# openSX70_SCHEMATIC_COMPLETE_NEW_BOARD_CO.net
KiCad netlist of a schematic drawn in EAGLE
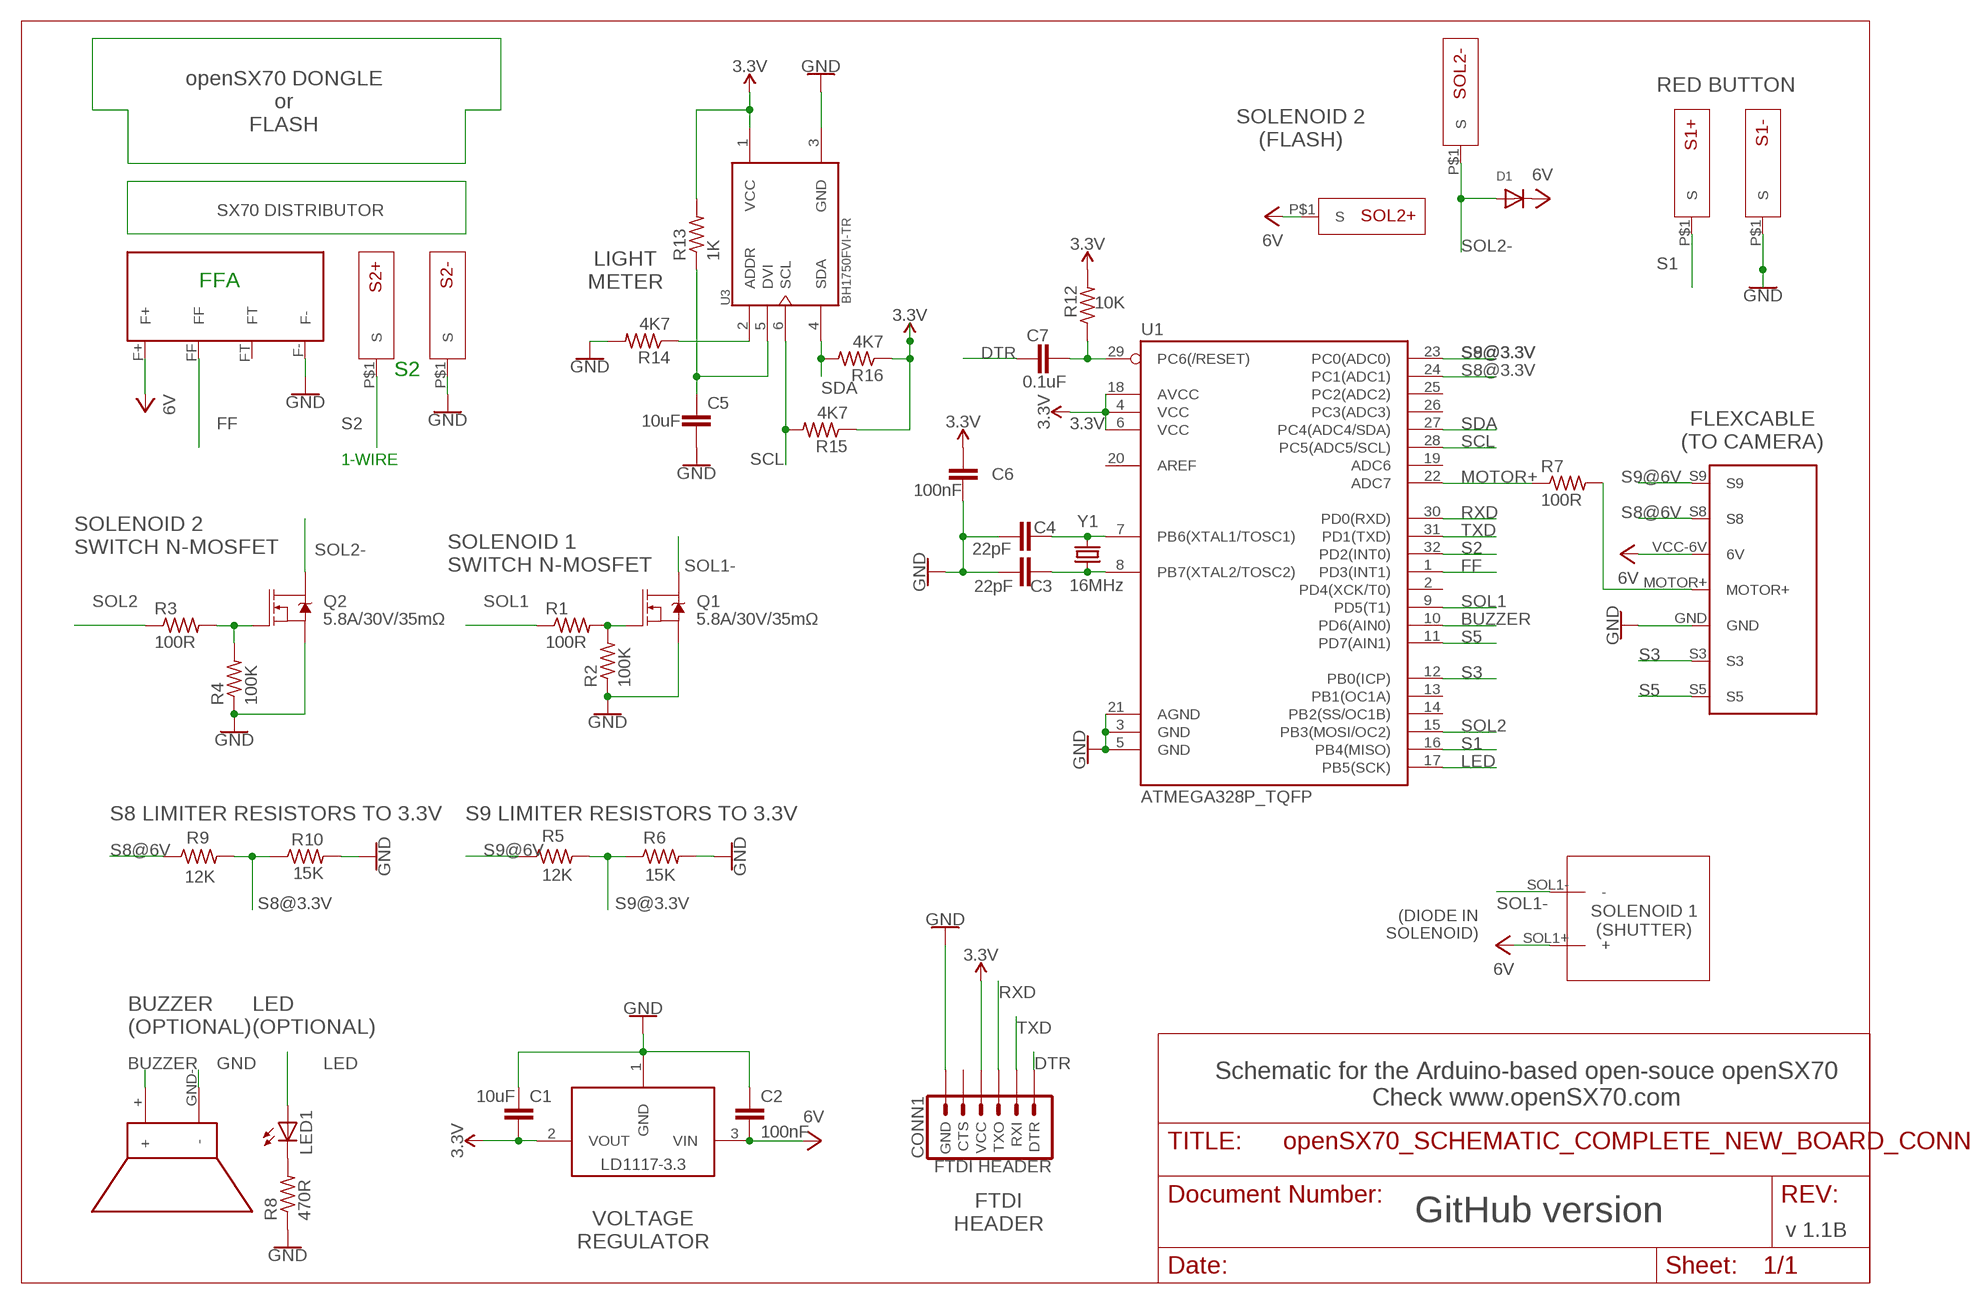
[diagram p0: schematic, sheet 1]

(export (version "E")
  (design (tool "Eeschema 10.0.6"))
  (components
    (comp (ref "BUZZ1")
      (value "CSET8-5G")
      (footprint "eagle-import:CSET8-5G_PACKAGE")
      (libsource (lib "eagle-import") (part "CSET8-5G"))
    )
    (comp (ref "C1")
      (value "10uF")
      (footprint "eagle-import:0603")
      (libsource (lib "eagle-import") (part "10UF-0603-6.3V-20%"))
    )
    (comp (ref "C2")
      (value "100nF")
      (footprint "eagle-import:C0603K")
      (libsource (lib "eagle-import") (part "C-EUC0603K"))
    )
    (comp (ref "C3")
      (value "22pF")
      (footprint "eagle-import:0603")
      (libsource (lib "eagle-import") (part "22PF-0603-50V-5%"))
    )
    (comp (ref "C4")
      (value "22pF")
      (footprint "eagle-import:0603")
      (libsource (lib "eagle-import") (part "22PF-0603-50V-5%"))
    )
    (comp (ref "C5")
      (value "10uF")
      (footprint "eagle-import:0603")
      (libsource (lib "eagle-import") (part "10UF-0603-6.3V-20%"))
    )
    (comp (ref "C6")
      (value "100nF")
      (footprint "eagle-import:C0805")
      (libsource (lib "eagle-import") (part "resistor_C-EUC0805"))
    )
    (comp (ref "C7")
      (value "0.1uF")
      (footprint "eagle-import:0603")
      (libsource (lib "eagle-import") (part "0.1UF-0603-25V-(+80/-20%)"))
    )
    (comp (ref "CONN1")
      (value "FTDI HEADER")
      (footprint "eagle-import:1X06")
      (libsource (lib "eagle-import") (part "6_PIN_SERIAL_TARGET"))
    )
    (comp (ref "D1")
      (value "DIODESOD-523")
      (footprint "eagle-import:SOD-523")
      (libsource (lib "eagle-import") (part "DIODESOD-523"))
    )
    (comp (ref "LD11173.3V")
      (value "LD1117 3.3V")
      (footprint "eagle-import:SOT223")
      (fields (field (name "MF") "Advanced Monolithic Systems") (field (name "MP") "AMS1117-5.0"))
      (libsource (lib "eagle-import") (part "LD1117-3.3"))
    )
    (comp (ref "LED1")
      (value "LEDCHIPLED_0805")
      (footprint "eagle-import:CHIPLED_0805")
      (libsource (lib "eagle-import") (part "LEDCHIPLED_0805"))
    )
    (comp (ref "Q1")
      (value "5.8A/30V/35mΩ")
      (footprint "eagle-import:SOT23-3")
      (libsource (lib "eagle-import") (part "MOSFET-NCH-AO3404A"))
    )
    (comp (ref "Q2")
      (value "5.8A/30V/35mΩ")
      (footprint "eagle-import:SOT23-3")
      (libsource (lib "eagle-import") (part "MOSFET-NCH-AO3404A"))
    )
    (comp (ref "R1")
      (value "100R")
      (footprint "eagle-import:R0603")
      (libsource (lib "eagle-import") (part "R-US_R0603"))
    )
    (comp (ref "R2")
      (value "100K")
      (footprint "eagle-import:R0603")
      (libsource (lib "eagle-import") (part "R-US_R0603"))
    )
    (comp (ref "R3")
      (value "100R")
      (footprint "eagle-import:R0603")
      (libsource (lib "eagle-import") (part "R-US_R0603"))
    )
    (comp (ref "R4")
      (value "100K")
      (footprint "eagle-import:R0603")
      (libsource (lib "eagle-import") (part "R-US_R0603"))
    )
    (comp (ref "R5")
      (value "12K")
      (footprint "eagle-import:R0603")
      (libsource (lib "eagle-import") (part "R-US_R0603"))
    )
    (comp (ref "R6")
      (value "15K")
      (footprint "eagle-import:R0603")
      (libsource (lib "eagle-import") (part "R-US_R0603"))
    )
    (comp (ref "R7")
      (value "100R")
      (footprint "eagle-import:R0603")
      (libsource (lib "eagle-import") (part "R-US_R0603"))
    )
    (comp (ref "R8")
      (value "470R")
      (footprint "eagle-import:R0603")
      (libsource (lib "eagle-import") (part "R-US_R0603"))
    )
    (comp (ref "R9")
      (value "12K")
      (footprint "eagle-import:R0603")
      (libsource (lib "eagle-import") (part "R-US_R0603"))
    )
    (comp (ref "R10")
      (value "15K")
      (footprint "eagle-import:R0603")
      (libsource (lib "eagle-import") (part "R-US_R0603"))
    )
    (comp (ref "R12")
      (value "10K")
      (footprint "eagle-import:R0603")
      (libsource (lib "eagle-import") (part "R-US_R0603"))
    )
    (comp (ref "R13")
      (value "1K")
      (footprint "eagle-import:R0603")
      (libsource (lib "eagle-import") (part "R-US_R0603"))
    )
    (comp (ref "R14")
      (value "4K7")
      (footprint "eagle-import:R0603")
      (libsource (lib "eagle-import") (part "R-US_R0603"))
    )
    (comp (ref "R15")
      (value "4K7")
      (footprint "eagle-import:R0603")
      (libsource (lib "eagle-import") (part "R-US_R0603"))
    )
    (comp (ref "R16")
      (value "4K7")
      (footprint "eagle-import:R0603")
      (libsource (lib "eagle-import") (part "R-US_R0603"))
    )
    (comp (ref "S1+")
      (value "SX70_S-PAD")
      (footprint "eagle-import:SX70-S-PAD")
      (libsource (lib "eagle-import") (part "SX70_S-PAD"))
    )
    (comp (ref "S1-")
      (value "SX70_S-PAD")
      (footprint "eagle-import:SX70-S-PAD")
      (libsource (lib "eagle-import") (part "SX70_S-PAD"))
    )
    (comp (ref "S2+")
      (value "SX70_S-PAD")
      (footprint "eagle-import:SX70-S-PAD")
      (libsource (lib "eagle-import") (part "SX70_S-PAD"))
    )
    (comp (ref "S2-")
      (value "SX70_S-PAD")
      (footprint "eagle-import:SX70-S-PAD")
      (libsource (lib "eagle-import") (part "SX70_S-PAD"))
    )
    (comp (ref "SOL1")
      (value "SX70-SOLENOID1-2PADS")
      (footprint "eagle-import:SX70-SOLENOID1-2")
      (libsource (lib "eagle-import") (part "SX70-SOLENOID1-2PADS"))
    )
    (comp (ref "SOL2+")
      (value "SX70_S-PAD")
      (footprint "eagle-import:SX70-S-PAD")
      (libsource (lib "eagle-import") (part "SX70_S-PAD"))
    )
    (comp (ref "SOL2-")
      (value "SX70_S-PAD")
      (footprint "eagle-import:SX70-S-PAD")
      (libsource (lib "eagle-import") (part "SX70_S-PAD"))
    )
    (comp (ref "U$1")
      (value "SX70-7-PAD")
      (footprint "eagle-import:SX70-7-PAD")
      (libsource (lib "eagle-import") (part "SX70-7-PAD"))
    )
    (comp (ref "U$2")
      (value "SX70-FFA-PAD")
      (footprint "eagle-import:FFA-PAD-PACKAGE")
      (libsource (lib "eagle-import") (part "SX70-FFA-PAD"))
    )
    (comp (ref "U1")
      (value "ATMEGA328P_TQFP")
      (footprint "eagle-import:TQFP32-08")
      (libsource (lib "eagle-import") (part "ATMEGA328P_TQFP"))
    )
    (comp (ref "U3")
      (value "BH1750FVI-TR")
      (footprint "eagle-import:SOTFL50P300X75-6N")
      (fields (field (name "MF") "Rohm"))
      (libsource (lib "eagle-import") (part "BH1750FVI-TR"))
    )
    (comp (ref "Y1")
      (value "16MHz")
      (footprint "eagle-import:CRYSTAL-SMD-5X3.2-4PAD")
      (libsource (lib "eagle-import") (part "CRYSTAL-16MHZSMD-5X3.2"))
    )
  )
  (nets
    (net (code "1") (name "/BUZZER") (class "Default")
      (node (ref "BUZZ1") (pin "+") (pinfunction "+_+") (pintype "bidirectional"))
      (node (ref "U1") (pin "10") (pinfunction "PD6(AIN0)_10") (pintype "bidirectional"))
    )
    (net (code "2") (name "/DTR") (class "Default")
      (node (ref "C7") (pin "1") (pinfunction "1_1") (pintype "passive"))
      (node (ref "CONN1") (pin "1") (pinfunction "DTR_1") (pintype "passive"))
    )
    (net (code "3") (name "/FF") (class "Default")
      (node (ref "U$2") (pin "FF") (pinfunction "FF_FF") (pintype "bidirectional"))
      (node (ref "U1") (pin "1") (pinfunction "PD3(INT1)_1") (pintype "bidirectional"))
    )
    (net (code "4") (name "/LED") (class "Default")
      (node (ref "LED1") (pin "A") (pinfunction "A_A") (pintype "passive"))
      (node (ref "U1") (pin "17") (pinfunction "PB5(SCK)_17") (pintype "bidirectional"))
    )
    (net (code "5") (name "/MOTOR+") (class "Default")
      (node (ref "R7") (pin "1") (pinfunction "1_1") (pintype "passive"))
      (node (ref "U1") (pin "22") (pinfunction "ADC7_22") (pintype "bidirectional"))
    )
    (net (code "6") (name "/RXD") (class "Default")
      (node (ref "CONN1") (pin "3") (pinfunction "TXO_3") (pintype "passive"))
      (node (ref "U1") (pin "30") (pinfunction "PD0(RXD)_30") (pintype "bidirectional"))
    )
    (net (code "7") (name "/S1") (class "Default")
      (node (ref "S1+") (pin "P$1") (pinfunction "S_P$1") (pintype "bidirectional"))
      (node (ref "U1") (pin "16") (pinfunction "PB4(MISO)_16") (pintype "bidirectional"))
    )
    (net (code "8") (name "/S2") (class "Default")
      (node (ref "S2+") (pin "P$1") (pinfunction "S_P$1") (pintype "bidirectional"))
      (node (ref "U1") (pin "32") (pinfunction "PD2(INT0)_32") (pintype "bidirectional"))
    )
    (net (code "9") (name "/S3") (class "Default")
      (node (ref "U$1") (pin "S3") (pinfunction "S3_S3") (pintype "bidirectional"))
      (node (ref "U1") (pin "12") (pinfunction "PB0(ICP)_12") (pintype "bidirectional"))
    )
    (net (code "10") (name "/S5") (class "Default")
      (node (ref "U$1") (pin "S5") (pinfunction "S5_S5") (pintype "bidirectional"))
      (node (ref "U1") (pin "11") (pinfunction "PD7(AIN1)_11") (pintype "bidirectional"))
    )
    (net (code "11") (name "/S8@3.3V") (class "Default")
      (node (ref "R10") (pin "1") (pinfunction "1_1") (pintype "passive"))
      (node (ref "R9") (pin "2") (pinfunction "2_2") (pintype "passive"))
      (node (ref "U1") (pin "24") (pinfunction "PC1(ADC1)_24") (pintype "bidirectional"))
    )
    (net (code "12") (name "/S8@6V") (class "Default")
      (node (ref "R9") (pin "1") (pinfunction "1_1") (pintype "passive"))
      (node (ref "U$1") (pin "S8") (pinfunction "S8_S8") (pintype "bidirectional"))
    )
    (net (code "13") (name "/S9@3.3V") (class "Default")
      (node (ref "R5") (pin "2") (pinfunction "2_2") (pintype "passive"))
      (node (ref "R6") (pin "1") (pinfunction "1_1") (pintype "passive"))
      (node (ref "U1") (pin "23") (pinfunction "PC0(ADC0)_23") (pintype "bidirectional"))
    )
    (net (code "14") (name "/S9@6V") (class "Default")
      (node (ref "R5") (pin "1") (pinfunction "1_1") (pintype "passive"))
      (node (ref "U$1") (pin "S9") (pinfunction "S9_S9") (pintype "bidirectional"))
    )
    (net (code "15") (name "/SCL") (class "Default")
      (node (ref "R15") (pin "2") (pinfunction "2_2") (pintype "passive"))
      (node (ref "U1") (pin "28") (pinfunction "PC5(ADC5/SCL)_28") (pintype "bidirectional"))
      (node (ref "U3") (pin "6") (pinfunction "SCL_6") (pintype "input"))
    )
    (net (code "16") (name "/SDA") (class "Default")
      (node (ref "R16") (pin "2") (pinfunction "2_2") (pintype "passive"))
      (node (ref "U1") (pin "27") (pinfunction "PC4(ADC4/SDA)_27") (pintype "bidirectional"))
      (node (ref "U3") (pin "4") (pinfunction "SDA_4") (pintype "bidirectional"))
    )
    (net (code "17") (name "/SOL1") (class "Default")
      (node (ref "R1") (pin "1") (pinfunction "1_1") (pintype "passive"))
      (node (ref "U1") (pin "9") (pinfunction "PD5(T1)_9") (pintype "bidirectional"))
    )
    (net (code "18") (name "/SOL1-") (class "Default")
      (node (ref "Q1") (pin "3") (pinfunction "D_3") (pintype "bidirectional"))
      (node (ref "SOL1") (pin "SOL1-") (pinfunction "-_SOL1-") (pintype "bidirectional"))
    )
    (net (code "19") (name "/SOL2") (class "Default")
      (node (ref "R3") (pin "1") (pinfunction "1_1") (pintype "passive"))
      (node (ref "U1") (pin "15") (pinfunction "PB3(MOSI/OC2)_15") (pintype "bidirectional"))
    )
    (net (code "20") (name "/SOL2-") (class "Default")
      (node (ref "D1") (pin "A") (pinfunction "A_A") (pintype "passive"))
      (node (ref "Q2") (pin "3") (pinfunction "D_3") (pintype "bidirectional"))
      (node (ref "SOL2-") (pin "P$1") (pinfunction "S_P$1") (pintype "bidirectional"))
    )
    (net (code "21") (name "/TXD") (class "Default")
      (node (ref "CONN1") (pin "2") (pinfunction "RXI_2") (pintype "passive"))
      (node (ref "U1") (pin "31") (pinfunction "PD1(TXD)_31") (pintype "bidirectional"))
    )
    (net (code "22") (name "3.3V") (class "Default")
      (node (ref "C1") (pin "2") (pinfunction "2_2") (pintype "passive"))
      (node (ref "C6") (pin "1") (pinfunction "1_1") (pintype "passive"))
      (node (ref "CONN1") (pin "4") (pinfunction "VCC_4") (pintype "passive"))
      (node (ref "LD11173.3V") (pin "2") (pinfunction "VOUT_2") (pintype "bidirectional"))
      (node (ref "R12") (pin "2") (pinfunction "2_2") (pintype "passive"))
      (node (ref "R13") (pin "2") (pinfunction "2_2") (pintype "passive"))
      (node (ref "R15") (pin "1") (pinfunction "1_1") (pintype "passive"))
      (node (ref "R16") (pin "1") (pinfunction "1_1") (pintype "passive"))
      (node (ref "U1") (pin "18") (pinfunction "AVCC_18") (pintype "bidirectional"))
      (node (ref "U1") (pin "4") (pinfunction "VCC_4") (pintype "bidirectional"))
      (node (ref "U1") (pin "6") (pinfunction "VCC_6") (pintype "bidirectional"))
      (node (ref "U3") (pin "1") (pinfunction "VCC_1") (pintype "power_in"))
    )
    (net (code "23") (name "6V") (class "Default")
      (node (ref "C2") (pin "2") (pinfunction "2_2") (pintype "passive"))
      (node (ref "D1") (pin "K") (pinfunction "C_K") (pintype "passive"))
      (node (ref "LD11173.3V") (pin "3") (pinfunction "VIN_3") (pintype "bidirectional"))
      (node (ref "SOL1") (pin "SOL1+") (pinfunction "+_SOL1+") (pintype "bidirectional"))
      (node (ref "SOL2+") (pin "P$1") (pinfunction "S_P$1") (pintype "bidirectional"))
      (node (ref "U$1") (pin "VCC-6V") (pinfunction "6V_VCC-6V") (pintype "bidirectional"))
      (node (ref "U$2") (pin "F+") (pinfunction "F+_F+") (pintype "bidirectional"))
    )
    (net (code "24") (name "GND") (class "Default")
      (node (ref "BUZZ1") (pin "GND-") (pinfunction "-_GND-") (pintype "bidirectional"))
      (node (ref "C1") (pin "1") (pinfunction "1_1") (pintype "passive"))
      (node (ref "C2") (pin "1") (pinfunction "1_1") (pintype "passive"))
      (node (ref "C3") (pin "1") (pinfunction "1_1") (pintype "passive"))
      (node (ref "C4") (pin "1") (pinfunction "1_1") (pintype "passive"))
      (node (ref "C5") (pin "2") (pinfunction "2_2") (pintype "passive"))
      (node (ref "C6") (pin "2") (pinfunction "2_2") (pintype "passive"))
      (node (ref "CONN1") (pin "6") (pinfunction "GND_6") (pintype "passive"))
      (node (ref "LD11173.3V") (pin "1") (pinfunction "GND_1") (pintype "bidirectional"))
      (node (ref "Q1") (pin "2") (pinfunction "S_2") (pintype "bidirectional"))
      (node (ref "Q2") (pin "2") (pinfunction "S_2") (pintype "bidirectional"))
      (node (ref "R10") (pin "2") (pinfunction "2_2") (pintype "passive"))
      (node (ref "R14") (pin "2") (pinfunction "2_2") (pintype "passive"))
      (node (ref "R2") (pin "1") (pinfunction "1_1") (pintype "passive"))
      (node (ref "R4") (pin "1") (pinfunction "1_1") (pintype "passive"))
      (node (ref "R6") (pin "2") (pinfunction "2_2") (pintype "passive"))
      (node (ref "R8") (pin "1") (pinfunction "1_1") (pintype "passive"))
      (node (ref "S1-") (pin "P$1") (pinfunction "S_P$1") (pintype "bidirectional"))
      (node (ref "S2-") (pin "P$1") (pinfunction "S_P$1") (pintype "bidirectional"))
      (node (ref "U$1") (pin "GND") (pinfunction "GND_GND") (pintype "bidirectional"))
      (node (ref "U$2") (pin "F-") (pinfunction "F-_F-") (pintype "bidirectional"))
      (node (ref "U1") (pin "21") (pinfunction "AGND_21") (pintype "bidirectional"))
      (node (ref "U1") (pin "3") (pinfunction "GND_3") (pintype "bidirectional"))
      (node (ref "U1") (pin "5") (pinfunction "GND_5") (pintype "bidirectional"))
      (node (ref "U3") (pin "3") (pinfunction "GND_3") (pintype "power_in"))
    )
    (net (code "25") (name "Net-(LED1-PadC)") (class "Default")
      (node (ref "LED1") (pin "C") (pinfunction "C_C") (pintype "passive"))
      (node (ref "R8") (pin "2") (pinfunction "2_2") (pintype "passive"))
    )
    (net (code "26") (name "Net-(Q1-G)") (class "Default")
      (node (ref "Q1") (pin "1") (pinfunction "G_1") (pintype "bidirectional"))
      (node (ref "R1") (pin "2") (pinfunction "2_2") (pintype "passive"))
      (node (ref "R2") (pin "2") (pinfunction "2_2") (pintype "passive"))
    )
    (net (code "27") (name "Net-(Q2-G)") (class "Default")
      (node (ref "Q2") (pin "1") (pinfunction "G_1") (pintype "bidirectional"))
      (node (ref "R3") (pin "2") (pinfunction "2_2") (pintype "passive"))
      (node (ref "R4") (pin "2") (pinfunction "2_2") (pintype "passive"))
    )
    (net (code "28") (name "Net-(R7-Pad2)") (class "Default")
      (node (ref "R7") (pin "2") (pinfunction "2_2") (pintype "passive"))
      (node (ref "U$1") (pin "MOTOR+") (pinfunction "MOTOR+_MOTOR+") (pintype "bidirectional"))
    )
    (net (code "29") (name "Net-(U1-PB6(XTAL1{slash}TOSC1))") (class "Default")
      (node (ref "C4") (pin "2") (pinfunction "2_2") (pintype "passive"))
      (node (ref "U1") (pin "7") (pinfunction "PB6(XTAL1/TOSC1)_7") (pintype "bidirectional"))
      (node (ref "Y1") (pin "3") (pinfunction "2_3") (pintype "passive"))
    )
    (net (code "30") (name "Net-(U1-PB7(XTAL2{slash}TOSC2))") (class "Default")
      (node (ref "C3") (pin "2") (pinfunction "2_2") (pintype "passive"))
      (node (ref "U1") (pin "8") (pinfunction "PB7(XTAL2/TOSC2)_8") (pintype "bidirectional"))
      (node (ref "Y1") (pin "1") (pinfunction "1_1") (pintype "passive"))
    )
    (net (code "31") (name "Net-(U1-PC6({slash}RESET))") (class "Default")
      (node (ref "C7") (pin "2") (pinfunction "2_2") (pintype "passive"))
      (node (ref "R12") (pin "1") (pinfunction "1_1") (pintype "passive"))
      (node (ref "U1") (pin "29") (pinfunction "PC6(/RESET)_29") (pintype "bidirectional"))
    )
    (net (code "32") (name "Net-(U3-ADDR)") (class "Default")
      (node (ref "R14") (pin "1") (pinfunction "1_1") (pintype "passive"))
      (node (ref "U3") (pin "2") (pinfunction "ADDR_2") (pintype "input"))
    )
    (net (code "33") (name "Net-(U3-DVI)") (class "Default")
      (node (ref "C5") (pin "1") (pinfunction "1_1") (pintype "passive"))
      (node (ref "R13") (pin "1") (pinfunction "1_1") (pintype "passive"))
      (node (ref "U3") (pin "5") (pinfunction "DVI_5") (pintype "input"))
    )
    (net (code "34") (name "unconnected-(CONN1-CTS-Pad5)") (class "Default")
      (node (ref "CONN1") (pin "5") (pinfunction "CTS_5") (pintype "passive"))
    )
    (net (code "35") (name "unconnected-(U$2-PadFT)") (class "Default")
      (node (ref "U$2") (pin "FT") (pinfunction "FT_FT") (pintype "bidirectional"))
    )
    (net (code "36") (name "unconnected-(U1-ADC6-Pad19)") (class "Default")
      (node (ref "U1") (pin "19") (pinfunction "ADC6_19") (pintype "bidirectional"))
    )
    (net (code "37") (name "unconnected-(U1-AREF-Pad20)") (class "Default")
      (node (ref "U1") (pin "20") (pinfunction "AREF_20") (pintype "bidirectional"))
    )
    (net (code "38") (name "unconnected-(U1-PB1(OC1A)-Pad13)") (class "Default")
      (node (ref "U1") (pin "13") (pinfunction "PB1(OC1A)_13") (pintype "bidirectional"))
    )
    (net (code "39") (name "unconnected-(U1-PB2(SS{slash}OC1B)-Pad14)") (class "Default")
      (node (ref "U1") (pin "14") (pinfunction "PB2(SS/OC1B)_14") (pintype "bidirectional"))
    )
    (net (code "40") (name "unconnected-(U1-PC2(ADC2)-Pad25)") (class "Default")
      (node (ref "U1") (pin "25") (pinfunction "PC2(ADC2)_25") (pintype "bidirectional"))
    )
    (net (code "41") (name "unconnected-(U1-PC3(ADC3)-Pad26)") (class "Default")
      (node (ref "U1") (pin "26") (pinfunction "PC3(ADC3)_26") (pintype "bidirectional"))
    )
    (net (code "42") (name "unconnected-(U1-PD4(XCK{slash}T0)-Pad2)") (class "Default")
      (node (ref "U1") (pin "2") (pinfunction "PD4(XCK/T0)_2") (pintype "bidirectional"))
    )
  )
)
